# Sheet1.net
KiCad netlist of a schematic drawn in Altium Designer
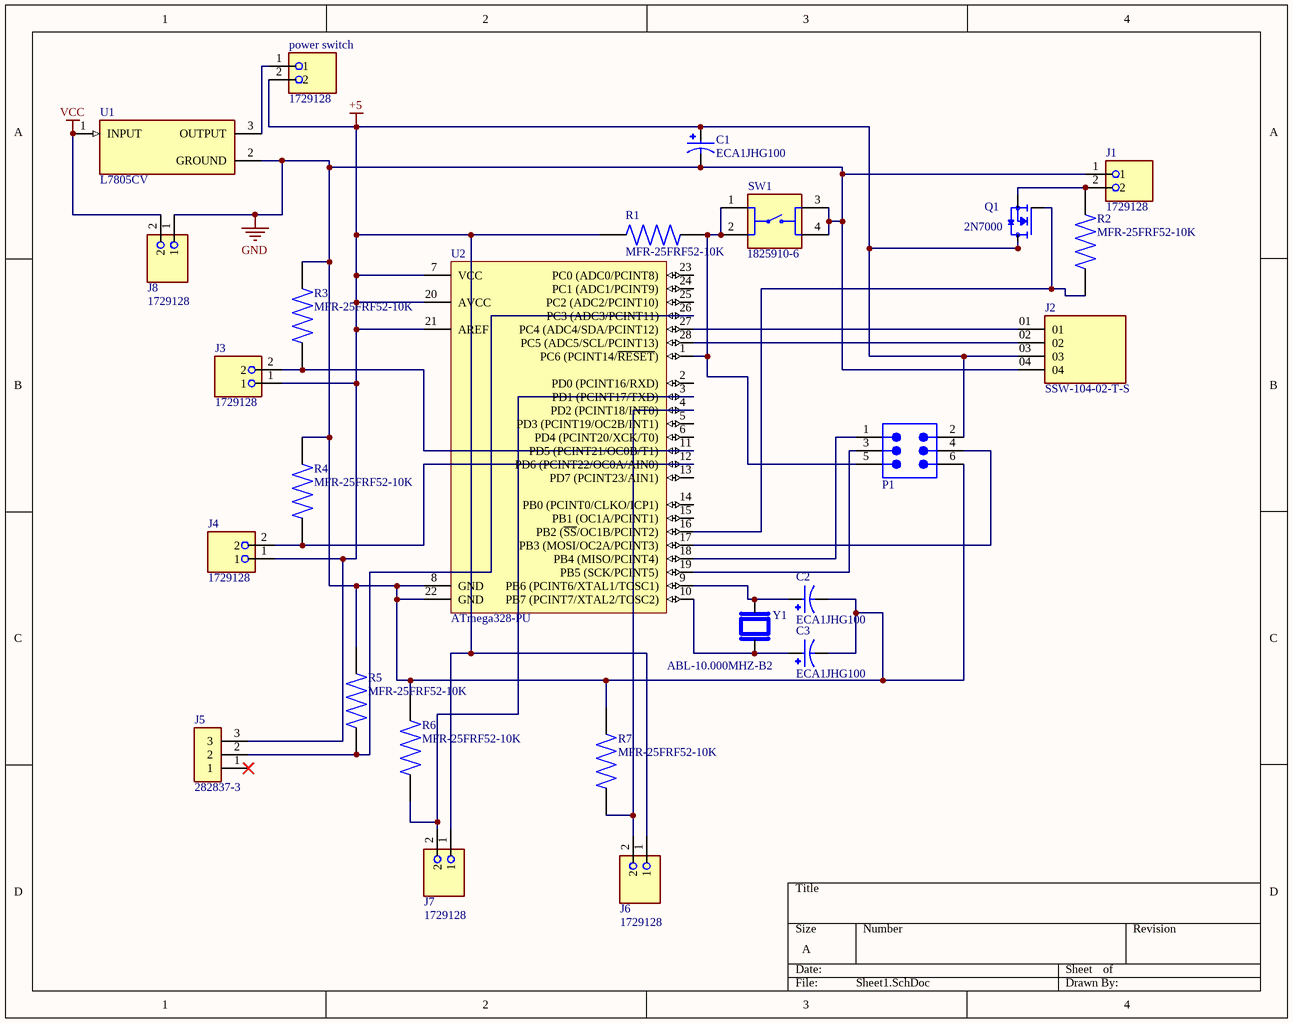
[diagram p0: Sheet1.SchDoc]

(export (version "E")
  (design (tool "Eeschema 10.0.6"))
  (components
    (comp (ref "C1")
      (value "ECA1JHG100")
      (footprint "CAPPRD200W50D500H1100")
      (description "NHG-A")
      (fields (field (name "MF") "Panasonic"))
      (libsource (lib "") (part "ECA1JHG100_1"))
    )
    (comp (ref "C2")
      (value "ECA1JHG100")
      (footprint "CAPPRD200W50D500H1100")
      (description "NHG-A")
      (fields (field (name "MF") "Panasonic"))
      (libsource (lib "Capacitor_ThroughHole") (part "ECA1JHG100"))
    )
    (comp (ref "C3")
      (value "ECA1JHG100")
      (footprint "CAPPRD200W50D500H1100")
      (description "NHG-A")
      (fields (field (name "MF") "Panasonic"))
      (libsource (lib "Capacitor_ThroughHole") (part "ECA1JHG100"))
    )
    (comp (ref "J1")
      (value "1729128")
      (footprint "PHOENIX_1729128")
      (fields (field (name "MF") "Phoenix Contact"))
      (libsource (lib "") (part "1729128_1"))
    )
    (comp (ref "J2")
      (value "SSW-104-02-T-S")
      (footprint "SAMTEC_SSW-104-02-T-S")
      (fields (field (name "MF") "Samtec Inc."))
      (libsource (lib "SSW-104-02-T-S") (part "SSW-104-02-T-S"))
    )
    (comp (ref "J3")
      (value "1729128")
      (footprint "PHOENIX_1729128")
      (fields (field (name "MF") "Phoenix Contact"))
      (libsource (lib "2pinBlock") (part "1729128"))
    )
    (comp (ref "J4")
      (value "1729128")
      (footprint "PHOENIX_1729128")
      (fields (field (name "MF") "Phoenix Contact"))
      (libsource (lib "2pinBlock") (part "1729128"))
    )
    (comp (ref "J5")
      (value "282837-3")
      (footprint "TE_282837-3")
      (description "TERMI-BLOK PCB MOUNT 3P")
      (libsource (lib "3pinBlock") (part "282837-3"))
    )
    (comp (ref "J6")
      (value "1729128")
      (footprint "PHOENIX_1729128")
      (fields (field (name "MF") "Phoenix Contact"))
      (libsource (lib "") (part "1729128_2"))
    )
    (comp (ref "J7")
      (value "1729128")
      (footprint "PHOENIX_1729128")
      (fields (field (name "MF") "Phoenix Contact"))
      (libsource (lib "") (part "1729128_2"))
    )
    (comp (ref "J8")
      (value "1729128")
      (footprint "PHOENIX_1729128")
      (fields (field (name "MF") "Phoenix Contact"))
      (libsource (lib "") (part "1729128_2"))
    )
    (comp (ref "P1")
      (value "61200621621")
      (footprint "61200621621")
      (description "WR-BHD Male Box Header, THT Straight, pitch 2.54mm, 2 row, 6 pin")
      (fields (field (name "MANUFACTURER") "Wurth Elektronik"))
      (libsource (lib "Altium_WR-BHD_rev23a") (part "61200621621"))
    )
    (comp (ref "power switch")
      (value "1729128")
      (footprint "PHOENIX_1729128")
      (fields (field (name "MF") "Phoenix Contact"))
      (libsource (lib "") (part "1729128_1"))
    )
    (comp (ref "Q1")
      (value "2N7000")
      (footprint "TO92254P458H750-3")
      (description "N-Channel 60 V 200mA (Ta) Through Hole TO-92")
      (fields (field (name "MF") "NTE Electronics, Inc."))
      (libsource (lib "Mosfet_2N7000") (part "2N7000"))
    )
    (comp (ref "R1")
      (value "MFR-25FRF52-10K")
      (footprint "RESAD1100W55L680D260")
      (description "10.5 kOhms Â±1% 0.25W, 1/4W Through Hole Resistor Axial - Metal Film")
      (fields (field (name "MF") "Yageo"))
      (libsource (lib "Resistor_ThroughHole") (part "MFR-25FRF52-10K"))
    )
    (comp (ref "R2")
      (value "MFR-25FRF52-10K")
      (footprint "RESAD1100W55L680D260")
      (description "10.5 kOhms Â±1% 0.25W, 1/4W Through Hole Resistor Axial - Metal Film")
      (fields (field (name "MF") "Yageo"))
      (libsource (lib "Resistor_ThroughHole") (part "MFR-25FRF52-10K"))
    )
    (comp (ref "R3")
      (value "MFR-25FRF52-10K")
      (footprint "RESAD1100W55L680D260")
      (description "10.5 kOhms Â±1% 0.25W, 1/4W Through Hole Resistor Axial - Metal Film")
      (fields (field (name "MF") "Yageo"))
      (libsource (lib "Resistor_ThroughHole") (part "MFR-25FRF52-10K"))
    )
    (comp (ref "R4")
      (value "MFR-25FRF52-10K")
      (footprint "RESAD1100W55L680D260")
      (description "10.5 kOhms Â±1% 0.25W, 1/4W Through Hole Resistor Axial - Metal Film")
      (fields (field (name "MF") "Yageo"))
      (libsource (lib "Resistor_ThroughHole") (part "MFR-25FRF52-10K"))
    )
    (comp (ref "R5")
      (value "MFR-25FRF52-10K")
      (footprint "RESAD1100W55L680D260")
      (description "10.5 kOhms Â±1% 0.25W, 1/4W Through Hole Resistor Axial - Metal Film")
      (fields (field (name "MF") "Yageo"))
      (libsource (lib "Resistor_ThroughHole") (part "MFR-25FRF52-10K"))
    )
    (comp (ref "R6")
      (value "MFR-25FRF52-10K")
      (footprint "RESAD1100W55L680D260")
      (description "10.5 kOhms Â±1% 0.25W, 1/4W Through Hole Resistor Axial - Metal Film")
      (fields (field (name "MF") "Yageo"))
      (libsource (lib "Resistor_ThroughHole") (part "MFR-25FRF52-10K"))
    )
    (comp (ref "R7")
      (value "MFR-25FRF52-10K")
      (footprint "RESAD1100W55L680D260")
      (description "10.5 kOhms Â±1% 0.25W, 1/4W Through Hole Resistor Axial - Metal Film")
      (fields (field (name "MF") "Yageo"))
      (libsource (lib "Resistor_ThroughHole") (part "MFR-25FRF52-10K"))
    )
    (comp (ref "SW1")
      (value "1825910-6")
      (footprint "SW_1825910-6-4")
      (description "Switch Push Button OFF (ON) SPST Round Button 0.05A 24VDC Momentary Contact PC Pins Thru-Hole")
      (fields (field (name "MF") "TE Connectivity") (field (name "DIGI-KEY_PART_NUMBER") "450-1650-ND"))
      (libsource (lib "1825910-6") (part "1825910-6"))
    )
    (comp (ref "U1")
      (value "L7805CV")
      (footprint "TO255P1040X460X1968-3")
      (description "Linear Voltage Regulator IC Positive Fixed 1 Output 1.5A TO-220")
      (fields (field (name "MF") "STMicroelectronics"))
      (libsource (lib "L7805CV") (part "L7805CV"))
    )
    (comp (ref "U2")
      (value "ATmega328-PU")
      (footprint "28P3")
      (libsource (lib "Altium Content Vault") (part "MC-8B-ATM48-IL28"))
    )
    (comp (ref "Y1")
      (value "ABL-10.000MHZ-B2")
      (footprint "XTAL_HC49P488W46L1150T500H350")
      (description "HC/49US (AT49) MICROPROCESSOR CRYSTAL")
      (fields (field (name "MF") "Abracon LLC"))
      (libsource (lib "Crystal_Ocillator") (part "ABL-10.000MHZ-B2"))
    )
  )
  (nets
    (net (code "1") (name "+5") (class "Default")
      (node (ref "C1") (pin "P") (pinfunction "P_P") (pintype "passive"))
      (node (ref "J2") (pin "03") (pinfunction "03_03") (pintype "passive"))
      (node (ref "J3") (pin "1") (pinfunction "1_1") (pintype "passive"))
      (node (ref "J4") (pin "1") (pinfunction "1_1") (pintype "passive"))
      (node (ref "J5") (pin "3") (pinfunction "3_3") (pintype "passive"))
      (node (ref "J6") (pin "1") (pinfunction "1_1") (pintype "passive"))
      (node (ref "J7") (pin "1") (pinfunction "1_1") (pintype "passive"))
      (node (ref "P1") (pin "2") (pinfunction "2_2") (pintype "passive"))
      (node (ref "Q1") (pin "3") (pinfunction "D_3") (pintype "passive"))
      (node (ref "R1") (pin "2") (pinfunction "2_2") (pintype "passive"))
      (node (ref "U2") (pin "20") (pinfunction "AVCC_20") (pintype "power_in"))
      (node (ref "U2") (pin "21") (pinfunction "AREF_21") (pintype "power_in"))
      (node (ref "U2") (pin "7") (pinfunction "VCC_7") (pintype "power_in"))
      (node (ref "power switch") (pin "2") (pinfunction "2_2") (pintype "passive"))
    )
    (net (code "2") (name "GND") (class "Default")
      (node (ref "C1") (pin "N") (pinfunction "N_N") (pintype "passive"))
      (node (ref "C2") (pin "N") (pinfunction "N_N") (pintype "passive"))
      (node (ref "C3") (pin "N") (pinfunction "N_N") (pintype "passive"))
      (node (ref "J1") (pin "1") (pinfunction "1_1") (pintype "passive"))
      (node (ref "J2") (pin "04") (pinfunction "04_04") (pintype "passive"))
      (node (ref "J8") (pin "1") (pinfunction "1_1") (pintype "passive"))
      (node (ref "P1") (pin "6") (pinfunction "6_6") (pintype "passive"))
      (node (ref "R3") (pin "2") (pinfunction "2_2") (pintype "passive"))
      (node (ref "R4") (pin "2") (pinfunction "2_2") (pintype "passive"))
      (node (ref "R5") (pin "2") (pinfunction "2_2") (pintype "passive"))
      (node (ref "R6") (pin "2") (pinfunction "2_2") (pintype "passive"))
      (node (ref "R7") (pin "2") (pinfunction "2_2") (pintype "passive"))
      (node (ref "SW1") (pin "3") (pinfunction "3_3") (pintype "passive"))
      (node (ref "SW1") (pin "4") (pinfunction "4_4") (pintype "passive"))
      (node (ref "U1") (pin "2") (pinfunction "GROUND_2") (pintype "power_in"))
      (node (ref "U2") (pin "22") (pinfunction "GND_22") (pintype "power_in"))
      (node (ref "U2") (pin "8") (pinfunction "GND_8") (pintype "power_in"))
    )
    (net (code "3") (name "Net-(Q1-G)") (class "Default")
      (node (ref "Q1") (pin "2") (pinfunction "G_2") (pintype "passive"))
      (node (ref "R2") (pin "1") (pinfunction "1_1") (pintype "passive"))
      (node (ref "U2") (pin "16") (pinfunction "PB2_(~{SS}/OC1B/PCINT2)_16") (pintype "bidirectional"))
    )
    (net (code "4") (name "Net-(Q1-S)") (class "Default")
      (node (ref "J1") (pin "2") (pinfunction "2_2") (pintype "passive"))
      (node (ref "Q1") (pin "1") (pinfunction "S_1") (pintype "passive"))
      (node (ref "R2") (pin "2") (pinfunction "2_2") (pintype "passive"))
    )
    (net (code "5") (name "Net-(U1-OUTPUT)") (class "Default")
      (node (ref "U1") (pin "3") (pinfunction "OUTPUT_3") (pintype "power_in"))
      (node (ref "power switch") (pin "1") (pinfunction "1_1") (pintype "passive"))
    )
    (net (code "6") (name "Net-(U2-PB3_(MOSI{slash}OC2A{slash}PCINT3))") (class "Default")
      (node (ref "P1") (pin "4") (pinfunction "4_4") (pintype "passive"))
      (node (ref "U2") (pin "17") (pinfunction "PB3_(MOSI/OC2A/PCINT3)_17") (pintype "bidirectional"))
    )
    (net (code "7") (name "Net-(U2-PB4_(MISO{slash}PCINT4))") (class "Default")
      (node (ref "P1") (pin "1") (pinfunction "1_1") (pintype "passive"))
      (node (ref "U2") (pin "18") (pinfunction "PB4_(MISO/PCINT4)_18") (pintype "bidirectional"))
    )
    (net (code "8") (name "Net-(U2-PB5_(SCK{slash}PCINT5))") (class "Default")
      (node (ref "P1") (pin "3") (pinfunction "3_3") (pintype "passive"))
      (node (ref "U2") (pin "19") (pinfunction "PB5_(SCK/PCINT5)_19") (pintype "bidirectional"))
    )
    (net (code "9") (name "Net-(U2-PB6_(PCINT6{slash}XTAL1{slash}TOSC1))") (class "Default")
      (node (ref "C2") (pin "P") (pinfunction "P_P") (pintype "passive"))
      (node (ref "U2") (pin "9") (pinfunction "PB6_(PCINT6/XTAL1/TOSC1)_9") (pintype "bidirectional"))
      (node (ref "Y1") (pin "2") (pinfunction "2_2") (pintype "passive"))
    )
    (net (code "10") (name "Net-(U2-PB7_(PCINT7{slash}XTAL2{slash}TOSC2))") (class "Default")
      (node (ref "C3") (pin "P") (pinfunction "P_P") (pintype "passive"))
      (node (ref "U2") (pin "10") (pinfunction "PB7_(PCINT7/XTAL2/TOSC2)_10") (pintype "bidirectional"))
      (node (ref "Y1") (pin "1") (pinfunction "1_1") (pintype "passive"))
    )
    (net (code "11") (name "Net-(U2-PC3_(ADC3{slash}PCINT11))") (class "Default")
      (node (ref "J5") (pin "2") (pinfunction "2_2") (pintype "passive"))
      (node (ref "R5") (pin "1") (pinfunction "1_1") (pintype "passive"))
      (node (ref "U2") (pin "26") (pinfunction "PC3_(ADC3/PCINT11)_26") (pintype "bidirectional"))
    )
    (net (code "12") (name "Net-(U2-PC4_(ADC4{slash}SDA{slash}PCINT12))") (class "Default")
      (node (ref "J2") (pin "01") (pinfunction "01_01") (pintype "passive"))
      (node (ref "U2") (pin "27") (pinfunction "PC4_(ADC4/SDA/PCINT12)_27") (pintype "bidirectional"))
    )
    (net (code "13") (name "Net-(U2-PC5_(ADC5{slash}SCL{slash}PCINT13))") (class "Default")
      (node (ref "J2") (pin "02") (pinfunction "02_02") (pintype "passive"))
      (node (ref "U2") (pin "28") (pinfunction "PC5_(ADC5/SCL/PCINT13)_28") (pintype "bidirectional"))
    )
    (net (code "14") (name "Net-(U2-PC6_(PCINT14{slash}~{RESET}))") (class "Default")
      (node (ref "P1") (pin "5") (pinfunction "5_5") (pintype "passive"))
      (node (ref "R1") (pin "1") (pinfunction "1_1") (pintype "passive"))
      (node (ref "SW1") (pin "1") (pinfunction "1_1") (pintype "passive"))
      (node (ref "SW1") (pin "2") (pinfunction "2_2") (pintype "passive"))
      (node (ref "U2") (pin "1") (pinfunction "PC6_(PCINT14/~{RESET})_1") (pintype "bidirectional"))
    )
    (net (code "15") (name "Net-(U2-PD1_(PCINT17{slash}TXD))") (class "Default")
      (node (ref "J7") (pin "2") (pinfunction "2_2") (pintype "passive"))
      (node (ref "R6") (pin "1") (pinfunction "1_1") (pintype "passive"))
      (node (ref "U2") (pin "3") (pinfunction "PD1_(PCINT17/TXD)_3") (pintype "bidirectional"))
    )
    (net (code "16") (name "Net-(U2-PD2_(PCINT18{slash}INT0))") (class "Default")
      (node (ref "J6") (pin "2") (pinfunction "2_2") (pintype "passive"))
      (node (ref "R7") (pin "1") (pinfunction "1_1") (pintype "passive"))
      (node (ref "U2") (pin "4") (pinfunction "PD2_(PCINT18/INT0)_4") (pintype "bidirectional"))
    )
    (net (code "17") (name "Net-(U2-PD5_(PCINT21{slash}OC0B{slash}T1))") (class "Default")
      (node (ref "J3") (pin "2") (pinfunction "2_2") (pintype "passive"))
      (node (ref "R3") (pin "1") (pinfunction "1_1") (pintype "passive"))
      (node (ref "U2") (pin "11") (pinfunction "PD5_(PCINT21/OC0B/T1)_11") (pintype "bidirectional"))
    )
    (net (code "18") (name "Net-(U2-PD6_(PCINT22{slash}OC0A{slash}AIN0))") (class "Default")
      (node (ref "J4") (pin "2") (pinfunction "2_2") (pintype "passive"))
      (node (ref "R4") (pin "1") (pinfunction "1_1") (pintype "passive"))
      (node (ref "U2") (pin "12") (pinfunction "PD6_(PCINT22/OC0A/AIN0)_12") (pintype "bidirectional"))
    )
    (net (code "19") (name "VCC") (class "Default")
      (node (ref "J8") (pin "2") (pinfunction "2_2") (pintype "passive"))
      (node (ref "U1") (pin "1") (pinfunction "INPUT_1") (pintype "input"))
    )
    (net (code "20") (name "unconnected-(J5-Pad1)") (class "Default")
      (node (ref "J5") (pin "1") (pinfunction "1_1") (pintype "passive+no_connect"))
    )
    (net (code "21") (name "unconnected-(U2-PB0_(PCINT0{slash}CLKO{slash}ICP1)-Pad14)") (class "Default")
      (node (ref "U2") (pin "14") (pinfunction "PB0_(PCINT0/CLKO/ICP1)_14") (pintype "bidirectional"))
    )
    (net (code "22") (name "unconnected-(U2-PB1_(OC1A{slash}PCINT1)-Pad15)") (class "Default")
      (node (ref "U2") (pin "15") (pinfunction "PB1_(OC1A/PCINT1)_15") (pintype "bidirectional"))
    )
    (net (code "23") (name "unconnected-(U2-PC0_(ADC0{slash}PCINT8)-Pad23)") (class "Default")
      (node (ref "U2") (pin "23") (pinfunction "PC0_(ADC0/PCINT8)_23") (pintype "bidirectional"))
    )
    (net (code "24") (name "unconnected-(U2-PC1_(ADC1{slash}PCINT9)-Pad24)") (class "Default")
      (node (ref "U2") (pin "24") (pinfunction "PC1_(ADC1/PCINT9)_24") (pintype "bidirectional"))
    )
    (net (code "25") (name "unconnected-(U2-PC2_(ADC2{slash}PCINT10)-Pad25)") (class "Default")
      (node (ref "U2") (pin "25") (pinfunction "PC2_(ADC2/PCINT10)_25") (pintype "bidirectional"))
    )
    (net (code "26") (name "unconnected-(U2-PD0_(PCINT16{slash}RXD)-Pad2)") (class "Default")
      (node (ref "U2") (pin "2") (pinfunction "PD0_(PCINT16/RXD)_2") (pintype "bidirectional"))
    )
    (net (code "27") (name "unconnected-(U2-PD3_(PCINT19{slash}OC2B{slash}INT1)-Pad5)") (class "Default")
      (node (ref "U2") (pin "5") (pinfunction "PD3_(PCINT19/OC2B/INT1)_5") (pintype "bidirectional"))
    )
    (net (code "28") (name "unconnected-(U2-PD4_(PCINT20{slash}XCK{slash}T0)-Pad6)") (class "Default")
      (node (ref "U2") (pin "6") (pinfunction "PD4_(PCINT20/XCK/T0)_6") (pintype "bidirectional"))
    )
    (net (code "29") (name "unconnected-(U2-PD7_(PCINT23{slash}AIN1)-Pad13)") (class "Default")
      (node (ref "U2") (pin "13") (pinfunction "PD7_(PCINT23/AIN1)_13") (pintype "bidirectional"))
    )
  )
)
